# Jalebi_Bai0_1.net
KiCad netlist of a schematic drawn in EAGLE
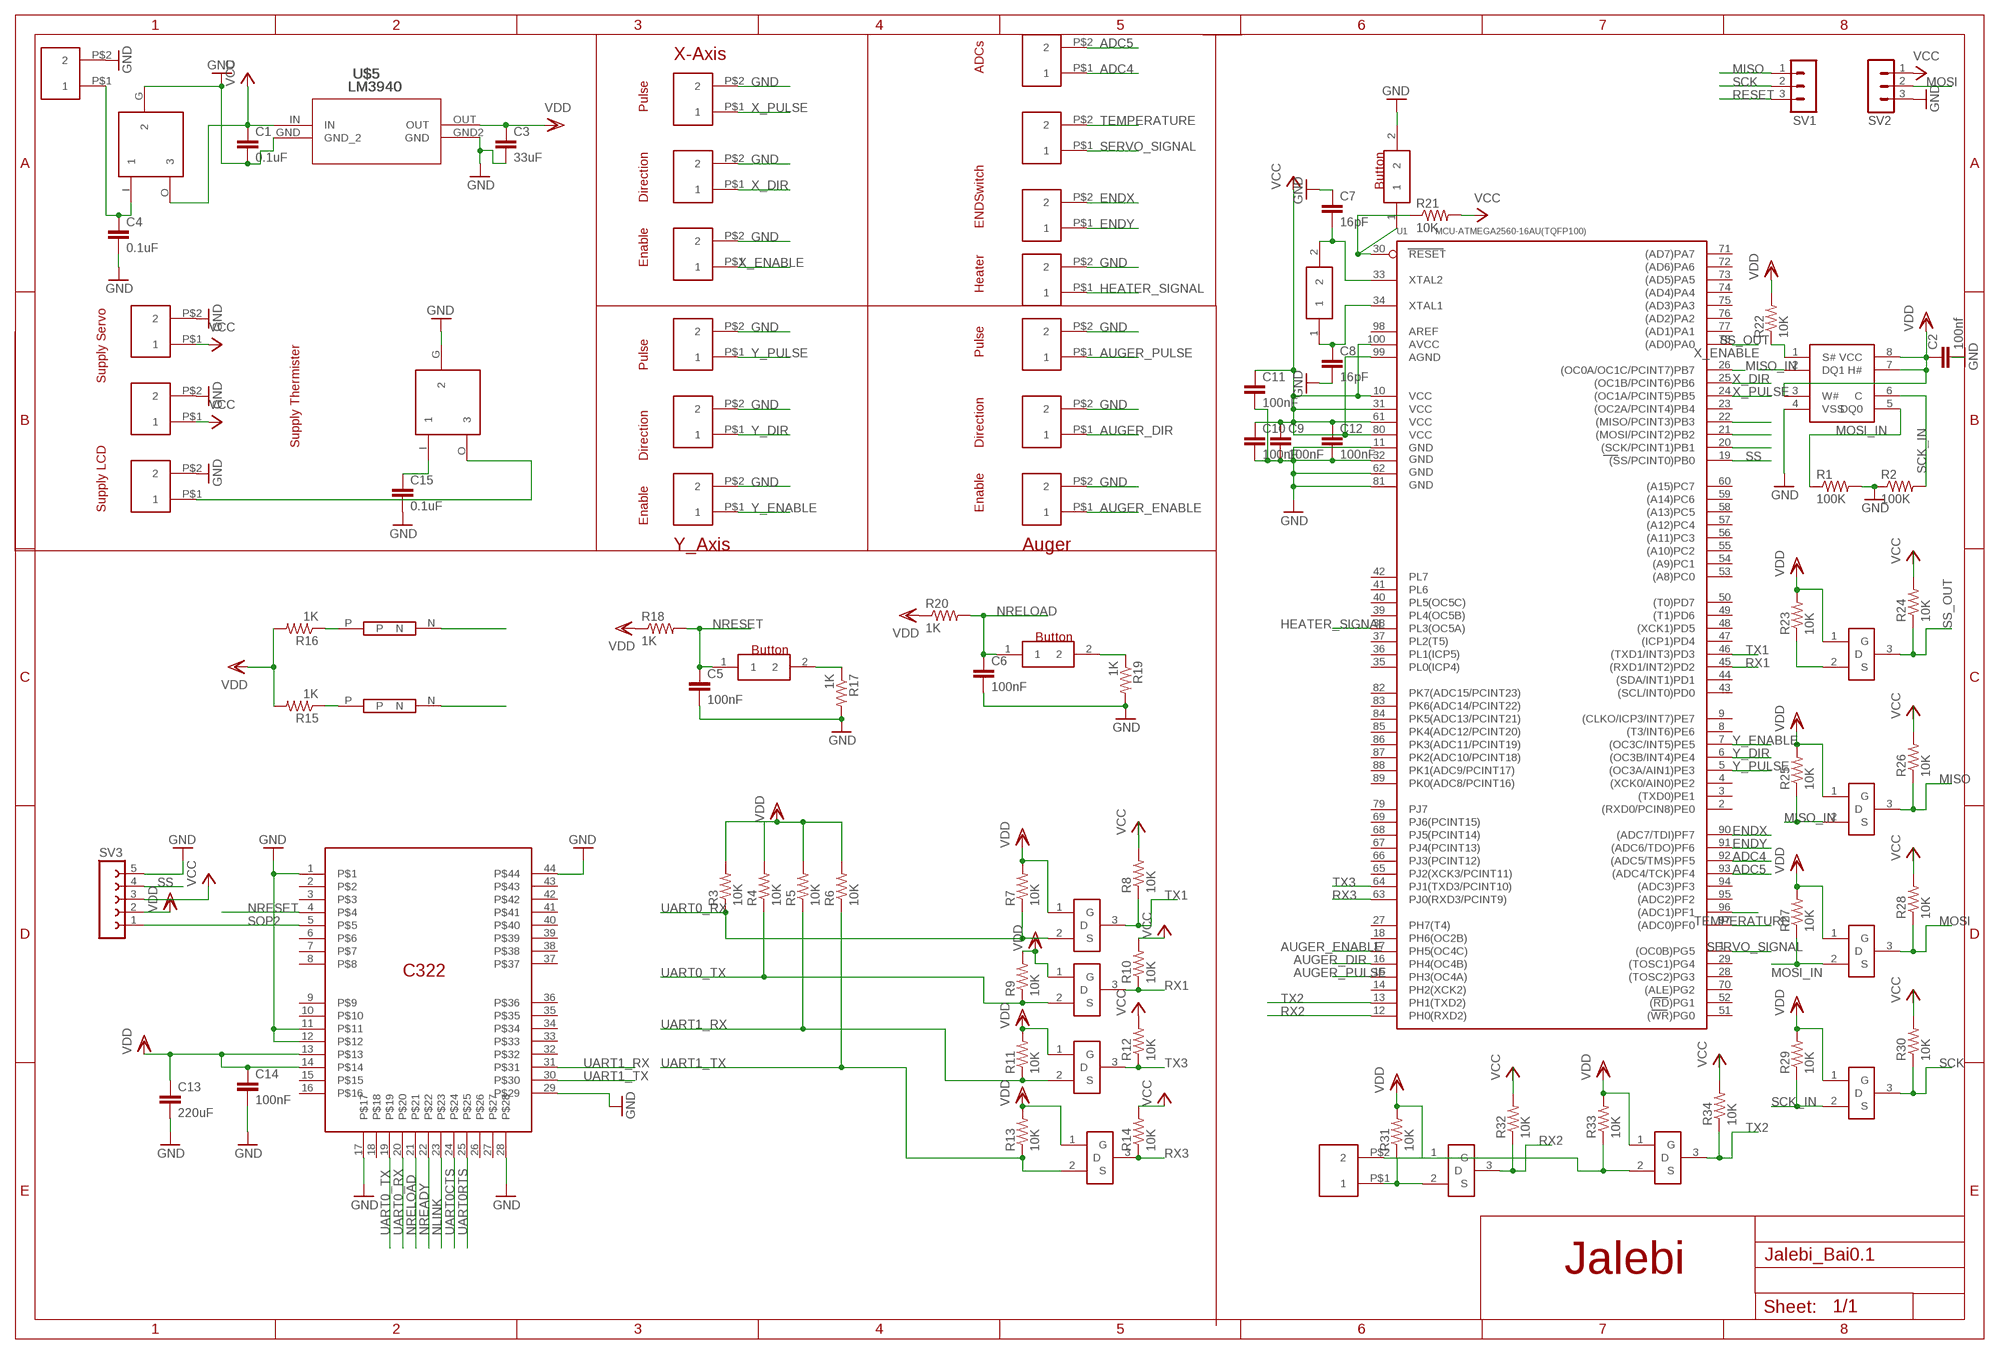
[diagram p0: schematic, sheet 1]

(export (version "E")
  (design (tool "Eeschema 10.0.6"))
  (components
    (comp (ref "C1")
      (value "0.1uF")
      (footprint "eagle-import:C0805")
      (libsource (lib "eagle-import") (part "C-EUC0805"))
    )
    (comp (ref "C2")
      (value "100nf")
      (footprint "eagle-import:C0805")
      (libsource (lib "eagle-import") (part "C-EUC0805"))
    )
    (comp (ref "C3")
      (value "33uF")
      (footprint "eagle-import:C0805")
      (libsource (lib "eagle-import") (part "C-EUC0805"))
    )
    (comp (ref "C4")
      (value "0.1uF")
      (footprint "eagle-import:C0805")
      (libsource (lib "eagle-import") (part "C-EUC0805"))
    )
    (comp (ref "C5")
      (value "100nF")
      (footprint "eagle-import:C0805")
      (libsource (lib "eagle-import") (part "C-EUC0805"))
    )
    (comp (ref "C6")
      (value "100nF")
      (footprint "eagle-import:C0805")
      (libsource (lib "eagle-import") (part "C-EUC0805"))
    )
    (comp (ref "C7")
      (value "16pF")
      (footprint "eagle-import:C0805")
      (libsource (lib "eagle-import") (part "C-EUC0805"))
    )
    (comp (ref "C8")
      (value "16pF")
      (footprint "eagle-import:C0805")
      (libsource (lib "eagle-import") (part "C-EUC0805"))
    )
    (comp (ref "C9")
      (value "100nF")
      (footprint "eagle-import:C0805")
      (libsource (lib "eagle-import") (part "C-EUC0805"))
    )
    (comp (ref "C10")
      (value "100nF")
      (footprint "eagle-import:C0805")
      (libsource (lib "eagle-import") (part "C-EUC0805"))
    )
    (comp (ref "C11")
      (value "100nF")
      (footprint "eagle-import:C0805")
      (libsource (lib "eagle-import") (part "C-EUC0805"))
    )
    (comp (ref "C12")
      (value "100nF")
      (footprint "eagle-import:C0805")
      (libsource (lib "eagle-import") (part "C-EUC0805"))
    )
    (comp (ref "C13")
      (value "220uF")
      (footprint "eagle-import:C0805")
      (libsource (lib "eagle-import") (part "C-EUC0805"))
    )
    (comp (ref "C14")
      (value "100nF")
      (footprint "eagle-import:C0805")
      (libsource (lib "eagle-import") (part "C-EUC0805"))
    )
    (comp (ref "C15")
      (value "0.1uF")
      (footprint "eagle-import:C0805")
      (libsource (lib "eagle-import") (part "C-EUC0805"))
    )
    (comp (ref "R1")
      (value "100K")
      (footprint "eagle-import:R0805")
      (libsource (lib "eagle-import") (part "R-US_R0805"))
    )
    (comp (ref "R2")
      (value "100K")
      (footprint "eagle-import:R0805")
      (libsource (lib "eagle-import") (part "R-US_R0805"))
    )
    (comp (ref "R3")
      (value "10K")
      (footprint "eagle-import:R0805")
      (libsource (lib "eagle-import") (part "R-US_R0805"))
    )
    (comp (ref "R4")
      (value "10K")
      (footprint "eagle-import:R0805")
      (libsource (lib "eagle-import") (part "R-US_R0805"))
    )
    (comp (ref "R5")
      (value "10K")
      (footprint "eagle-import:R0805")
      (libsource (lib "eagle-import") (part "R-US_R0805"))
    )
    (comp (ref "R6")
      (value "10K")
      (footprint "eagle-import:R0805")
      (libsource (lib "eagle-import") (part "R-US_R0805"))
    )
    (comp (ref "R7")
      (value "10K")
      (footprint "eagle-import:R0805")
      (libsource (lib "eagle-import") (part "R-US_R0805"))
    )
    (comp (ref "R8")
      (value "10K")
      (footprint "eagle-import:R0805")
      (libsource (lib "eagle-import") (part "R-US_R0805"))
    )
    (comp (ref "R9")
      (value "10K")
      (footprint "eagle-import:R0805")
      (libsource (lib "eagle-import") (part "R-US_R0805"))
    )
    (comp (ref "R10")
      (value "10K")
      (footprint "eagle-import:R0805")
      (libsource (lib "eagle-import") (part "R-US_R0805"))
    )
    (comp (ref "R11")
      (value "10K")
      (footprint "eagle-import:R0805")
      (libsource (lib "eagle-import") (part "R-US_R0805"))
    )
    (comp (ref "R12")
      (value "10K")
      (footprint "eagle-import:R0805")
      (libsource (lib "eagle-import") (part "R-US_R0805"))
    )
    (comp (ref "R13")
      (value "10K")
      (footprint "eagle-import:R0805")
      (libsource (lib "eagle-import") (part "R-US_R0805"))
    )
    (comp (ref "R14")
      (value "10K")
      (footprint "eagle-import:R0805")
      (libsource (lib "eagle-import") (part "R-US_R0805"))
    )
    (comp (ref "R15")
      (value "1K")
      (footprint "eagle-import:R0805")
      (libsource (lib "eagle-import") (part "R-US_R0805"))
    )
    (comp (ref "R16")
      (value "1K")
      (footprint "eagle-import:R0805")
      (libsource (lib "eagle-import") (part "R-US_R0805"))
    )
    (comp (ref "R17")
      (value "1K")
      (footprint "eagle-import:R0805")
      (libsource (lib "eagle-import") (part "R-US_R0805"))
    )
    (comp (ref "R18")
      (value "1K")
      (footprint "eagle-import:R0805")
      (libsource (lib "eagle-import") (part "R-US_R0805"))
    )
    (comp (ref "R19")
      (value "1K")
      (footprint "eagle-import:R0805")
      (libsource (lib "eagle-import") (part "R-US_R0805"))
    )
    (comp (ref "R20")
      (value "1K")
      (footprint "eagle-import:R0805")
      (libsource (lib "eagle-import") (part "R-US_R0805"))
    )
    (comp (ref "R21")
      (value "10K")
      (footprint "eagle-import:R0805")
      (libsource (lib "eagle-import") (part "R-US_R0805"))
    )
    (comp (ref "R22")
      (value "10K")
      (footprint "eagle-import:R0805")
      (libsource (lib "eagle-import") (part "R-US_R0805"))
    )
    (comp (ref "R23")
      (value "10K")
      (footprint "eagle-import:R0805")
      (libsource (lib "eagle-import") (part "R-US_R0805"))
    )
    (comp (ref "R24")
      (value "10K")
      (footprint "eagle-import:R0805")
      (libsource (lib "eagle-import") (part "R-US_R0805"))
    )
    (comp (ref "R25")
      (value "10K")
      (footprint "eagle-import:R0805")
      (libsource (lib "eagle-import") (part "R-US_R0805"))
    )
    (comp (ref "R26")
      (value "10K")
      (footprint "eagle-import:R0805")
      (libsource (lib "eagle-import") (part "R-US_R0805"))
    )
    (comp (ref "R27")
      (value "10K")
      (footprint "eagle-import:R0805")
      (libsource (lib "eagle-import") (part "R-US_R0805"))
    )
    (comp (ref "R28")
      (value "10K")
      (footprint "eagle-import:R0805")
      (libsource (lib "eagle-import") (part "R-US_R0805"))
    )
    (comp (ref "R29")
      (value "10K")
      (footprint "eagle-import:R0805")
      (libsource (lib "eagle-import") (part "R-US_R0805"))
    )
    (comp (ref "R30")
      (value "10K")
      (footprint "eagle-import:R0805")
      (libsource (lib "eagle-import") (part "R-US_R0805"))
    )
    (comp (ref "R31")
      (value "10K")
      (footprint "eagle-import:R0805")
      (libsource (lib "eagle-import") (part "R-US_R0805"))
    )
    (comp (ref "R32")
      (value "10K")
      (footprint "eagle-import:R0805")
      (libsource (lib "eagle-import") (part "R-US_R0805"))
    )
    (comp (ref "R33")
      (value "10K")
      (footprint "eagle-import:R0805")
      (libsource (lib "eagle-import") (part "R-US_R0805"))
    )
    (comp (ref "R34")
      (value "10K")
      (footprint "eagle-import:R0805")
      (libsource (lib "eagle-import") (part "R-US_R0805"))
    )
    (comp (ref "SUPPLY_LCD")
      (value "TERMINALBLOCK2PIN")
      (footprint "eagle-import:TERMINALBLOCK2")
      (libsource (lib "eagle-import") (part "TERMINALBLOCK2PIN"))
    )
    (comp (ref "SUPPLY_SERVO")
      (value "TERMINALBLOCK2PIN")
      (footprint "eagle-import:TERMINALBLOCK2")
      (libsource (lib "eagle-import") (part "TERMINALBLOCK2PIN"))
    )
    (comp (ref "SUPPLY_THERMISTER")
      (value "TERMINALBLOCK2PIN")
      (footprint "eagle-import:TERMINALBLOCK2")
      (libsource (lib "eagle-import") (part "TERMINALBLOCK2PIN"))
    )
    (comp (ref "SV1")
      (value "MA03-1")
      (footprint "eagle-import:MA03-1")
      (libsource (lib "eagle-import") (part "MA03-1"))
    )
    (comp (ref "SV2")
      (value "MA03-1")
      (footprint "eagle-import:MA03-1")
      (libsource (lib "eagle-import") (part "MA03-1"))
    )
    (comp (ref "SV3")
      (value "FE05-1")
      (footprint "eagle-import:FE05-1")
      (libsource (lib "eagle-import") (part "FE05-1"))
    )
    (comp (ref "U$1")
      (value "C322STD")
      (footprint "eagle-import:C322")
      (libsource (lib "eagle-import") (part "C322STD"))
    )
    (comp (ref "U$2")
      (value "7805")
      (footprint "eagle-import:7805")
      (libsource (lib "eagle-import") (part "7805"))
    )
    (comp (ref "U$3")
      (value "TERMINALBLOCK2PIN")
      (footprint "eagle-import:TERMINALBLOCK2")
      (libsource (lib "eagle-import") (part "TERMINALBLOCK2PIN"))
    )
    (comp (ref "U$4")
      (value "FLASHM25PX80")
      (footprint "eagle-import:SO08")
      (libsource (lib "eagle-import") (part "FLASHM25PX80"))
    )
    (comp (ref "U$5")
      (value "LM3940")
      (footprint "eagle-import:MP04A")
      (libsource (lib "eagle-import") (part "LM3940"))
    )
    (comp (ref "U$6")
      (value "BSS138")
      (footprint "eagle-import:SOT23")
      (libsource (lib "eagle-import") (part "BSS138"))
    )
    (comp (ref "U$7")
      (value "BSS138")
      (footprint "eagle-import:SOT23")
      (libsource (lib "eagle-import") (part "BSS138"))
    )
    (comp (ref "U$8")
      (value "BSS138")
      (footprint "eagle-import:SOT23")
      (libsource (lib "eagle-import") (part "BSS138"))
    )
    (comp (ref "U$9")
      (value "BSS138")
      (footprint "eagle-import:SOT23")
      (libsource (lib "eagle-import") (part "BSS138"))
    )
    (comp (ref "U$10")
      (value "LED(805)")
      (footprint "eagle-import:LED(805)")
      (libsource (lib "eagle-import") (part "LED(805)"))
    )
    (comp (ref "U$11")
      (value "LED(805)")
      (footprint "eagle-import:LED(805)")
      (libsource (lib "eagle-import") (part "LED(805)"))
    )
    (comp (ref "U$12")
      (value "BUTTON")
      (footprint "eagle-import:BUTTON")
      (libsource (lib "eagle-import") (part "BUTTON"))
    )
    (comp (ref "U$13")
      (value "BUTTON")
      (footprint "eagle-import:BUTTON")
      (libsource (lib "eagle-import") (part "BUTTON"))
    )
    (comp (ref "U$14")
      (value "TERMINALBLOCK2PIN")
      (footprint "eagle-import:TERMINALBLOCK2")
      (libsource (lib "eagle-import") (part "TERMINALBLOCK2PIN"))
    )
    (comp (ref "U$15")
      (value "CRYSTAL")
      (footprint "eagle-import:CRYSTAL")
      (libsource (lib "eagle-import") (part "CRYSTAL"))
    )
    (comp (ref "U$16")
      (value "BUTTON")
      (footprint "eagle-import:BUTTON")
      (libsource (lib "eagle-import") (part "BUTTON"))
    )
    (comp (ref "U$17")
      (value "BSS138")
      (footprint "eagle-import:SOT23")
      (libsource (lib "eagle-import") (part "BSS138"))
    )
    (comp (ref "U$18")
      (value "BSS138")
      (footprint "eagle-import:SOT23")
      (libsource (lib "eagle-import") (part "BSS138"))
    )
    (comp (ref "U$19")
      (value "BSS138")
      (footprint "eagle-import:SOT23")
      (libsource (lib "eagle-import") (part "BSS138"))
    )
    (comp (ref "U$20")
      (value "BSS138")
      (footprint "eagle-import:SOT23")
      (libsource (lib "eagle-import") (part "BSS138"))
    )
    (comp (ref "U$21")
      (value "BSS138")
      (footprint "eagle-import:SOT23")
      (libsource (lib "eagle-import") (part "BSS138"))
    )
    (comp (ref "U$22")
      (value "BSS138")
      (footprint "eagle-import:SOT23")
      (libsource (lib "eagle-import") (part "BSS138"))
    )
    (comp (ref "U$23")
      (value "TERMINALBLOCK2PIN")
      (footprint "eagle-import:TERMINALBLOCK2")
      (libsource (lib "eagle-import") (part "TERMINALBLOCK2PIN"))
    )
    (comp (ref "U$24")
      (value "TERMINALBLOCK2PIN")
      (footprint "eagle-import:TERMINALBLOCK2")
      (libsource (lib "eagle-import") (part "TERMINALBLOCK2PIN"))
    )
    (comp (ref "U$25")
      (value "7805")
      (footprint "eagle-import:7805")
      (libsource (lib "eagle-import") (part "7805"))
    )
    (comp (ref "U$26")
      (value "TERMINALBLOCK2PIN")
      (footprint "eagle-import:TERMINALBLOCK2")
      (libsource (lib "eagle-import") (part "TERMINALBLOCK2PIN"))
    )
    (comp (ref "U$27")
      (value "TERMINALBLOCK2PIN")
      (footprint "eagle-import:TERMINALBLOCK2")
      (libsource (lib "eagle-import") (part "TERMINALBLOCK2PIN"))
    )
    (comp (ref "U$28")
      (value "TERMINALBLOCK2PIN")
      (footprint "eagle-import:TERMINALBLOCK2")
      (libsource (lib "eagle-import") (part "TERMINALBLOCK2PIN"))
    )
    (comp (ref "U$29")
      (value "TERMINALBLOCK2PIN")
      (footprint "eagle-import:TERMINALBLOCK2")
      (libsource (lib "eagle-import") (part "TERMINALBLOCK2PIN"))
    )
    (comp (ref "U$30")
      (value "TERMINALBLOCK2PIN")
      (footprint "eagle-import:TERMINALBLOCK2")
      (libsource (lib "eagle-import") (part "TERMINALBLOCK2PIN"))
    )
    (comp (ref "U$31")
      (value "TERMINALBLOCK2PIN")
      (footprint "eagle-import:TERMINALBLOCK2")
      (libsource (lib "eagle-import") (part "TERMINALBLOCK2PIN"))
    )
    (comp (ref "U$32")
      (value "TERMINALBLOCK2PIN")
      (footprint "eagle-import:TERMINALBLOCK2")
      (libsource (lib "eagle-import") (part "TERMINALBLOCK2PIN"))
    )
    (comp (ref "U$34")
      (value "TERMINALBLOCK2PIN")
      (footprint "eagle-import:TERMINALBLOCK2")
      (libsource (lib "eagle-import") (part "TERMINALBLOCK2PIN"))
    )
    (comp (ref "U$35")
      (value "TERMINALBLOCK2PIN")
      (footprint "eagle-import:TERMINALBLOCK2")
      (libsource (lib "eagle-import") (part "TERMINALBLOCK2PIN"))
    )
    (comp (ref "U$36")
      (value "TERMINALBLOCK2PIN")
      (footprint "eagle-import:TERMINALBLOCK2")
      (libsource (lib "eagle-import") (part "TERMINALBLOCK2PIN"))
    )
    (comp (ref "U$37")
      (value "TERMINALBLOCK2PIN")
      (footprint "eagle-import:TERMINALBLOCK2")
      (libsource (lib "eagle-import") (part "TERMINALBLOCK2PIN"))
    )
    (comp (ref "U1")
      (value "MCU-ATMEGA2560-16AU(TQFP100)")
      (footprint "eagle-import:TQFP100-0.5-14X14MM")
      (fields (field (name "MF") "Atmel") (field (name "MP") "ATMEGA2560-16AU"))
      (libsource (lib "eagle-import") (part "MCU-ATMEGA2560-16AU(TQFP100)"))
    )
  )
  (nets
    (net (code "1") (name "/ADC4") (class "Default")
      (node (ref "U$24") (pin "P$1") (pinfunction "1_P$1") (pintype "bidirectional"))
      (node (ref "U1") (pin "92") (pinfunction "(ADC5/TMS)PF5_92") (pintype "bidirectional"))
    )
    (net (code "2") (name "/ADC5") (class "Default")
      (node (ref "U$24") (pin "P$2") (pinfunction "2_P$2") (pintype "bidirectional"))
      (node (ref "U1") (pin "93") (pinfunction "(ADC4/TCK)PF4_93") (pintype "bidirectional"))
    )
    (net (code "3") (name "/AUGER_DIR") (class "Default")
      (node (ref "U$36") (pin "P$1") (pinfunction "1_P$1") (pintype "bidirectional"))
      (node (ref "U1") (pin "16") (pinfunction "PH4(OC4B)_16") (pintype "bidirectional"))
    )
    (net (code "4") (name "/AUGER_ENABLE") (class "Default")
      (node (ref "U$37") (pin "P$1") (pinfunction "1_P$1") (pintype "bidirectional"))
      (node (ref "U1") (pin "17") (pinfunction "PH5(OC4C)_17") (pintype "bidirectional"))
    )
    (net (code "5") (name "/AUGER_PULSE") (class "Default")
      (node (ref "U$35") (pin "P$1") (pinfunction "1_P$1") (pintype "bidirectional"))
      (node (ref "U1") (pin "15") (pinfunction "PH3(OC4A)_15") (pintype "bidirectional"))
    )
    (net (code "6") (name "/ENDX") (class "Default")
      (node (ref "U$23") (pin "P$2") (pinfunction "2_P$2") (pintype "bidirectional"))
      (node (ref "U1") (pin "90") (pinfunction "(ADC7/TDI)PF7_90") (pintype "bidirectional"))
    )
    (net (code "7") (name "/ENDY") (class "Default")
      (node (ref "U$23") (pin "P$1") (pinfunction "1_P$1") (pintype "bidirectional"))
      (node (ref "U1") (pin "91") (pinfunction "(ADC6/TDO)PF6_91") (pintype "bidirectional"))
    )
    (net (code "8") (name "/HEATER_SIGNAL") (class "Default")
      (node (ref "U$34") (pin "P$1") (pinfunction "1_P$1") (pintype "bidirectional"))
      (node (ref "U1") (pin "38") (pinfunction "PL3(OC5A)_38") (pintype "bidirectional"))
    )
    (net (code "9") (name "/MISO") (class "Default")
      (node (ref "R26") (pin "1") (pinfunction "1_1") (pintype "passive"))
      (node (ref "SV1") (pin "1") (pinfunction "1_1") (pintype "passive"))
      (node (ref "U$18") (pin "3") (pinfunction "D_3") (pintype "bidirectional"))
      (node (ref "U1") (pin "22") (pinfunction "(MISO/PCINT3)PB3_22") (pintype "bidirectional"))
    )
    (net (code "10") (name "/MISO_IN") (class "Default")
      (node (ref "R25") (pin "1") (pinfunction "1_1") (pintype "passive"))
      (node (ref "U$18") (pin "2") (pinfunction "S_2") (pintype "bidirectional"))
      (node (ref "U$4") (pin "2") (pinfunction "DQ1_2") (pintype "bidirectional"))
    )
    (net (code "11") (name "/MOSI") (class "Default")
      (node (ref "R28") (pin "1") (pinfunction "1_1") (pintype "passive"))
      (node (ref "SV2") (pin "2") (pinfunction "2_2") (pintype "passive"))
      (node (ref "U$19") (pin "3") (pinfunction "D_3") (pintype "bidirectional"))
      (node (ref "U1") (pin "21") (pinfunction "(MOSI/PCINT2)PB2_21") (pintype "bidirectional"))
    )
    (net (code "12") (name "/MOSI_IN") (class "Default")
      (node (ref "R1") (pin "1") (pinfunction "1_1") (pintype "passive"))
      (node (ref "R27") (pin "1") (pinfunction "1_1") (pintype "passive"))
      (node (ref "U$19") (pin "2") (pinfunction "S_2") (pintype "bidirectional"))
      (node (ref "U$4") (pin "5") (pinfunction "DQ0_5") (pintype "bidirectional"))
    )
    (net (code "13") (name "/N$5") (class "Default")
      (node (ref "C15") (pin "1") (pinfunction "1_1") (pintype "passive"))
      (node (ref "C4") (pin "1") (pinfunction "1_1") (pintype "passive"))
      (node (ref "U$2") (pin "I") (pinfunction "1_I") (pintype "bidirectional"))
      (node (ref "U$25") (pin "I") (pinfunction "1_I") (pintype "bidirectional"))
      (node (ref "U$3") (pin "P$1") (pinfunction "1_P$1") (pintype "bidirectional"))
    )
    (net (code "14") (name "/NLINK") (class "Default")
      (node (ref "U$1") (pin "23") (pinfunction "P$23_23") (pintype "bidirectional"))
      (node (ref "U$10") (pin "N") (pinfunction "N_N") (pintype "bidirectional"))
    )
    (net (code "15") (name "/NREADY") (class "Default")
      (node (ref "U$1") (pin "22") (pinfunction "P$22_22") (pintype "bidirectional"))
      (node (ref "U$11") (pin "N") (pinfunction "N_N") (pintype "bidirectional"))
    )
    (net (code "16") (name "/NRELOAD") (class "Default")
      (node (ref "C6") (pin "1") (pinfunction "1_1") (pintype "passive"))
      (node (ref "R20") (pin "2") (pinfunction "2_2") (pintype "passive"))
      (node (ref "U$1") (pin "21") (pinfunction "P$21_21") (pintype "bidirectional"))
      (node (ref "U$13") (pin "1") (pinfunction "1_1") (pintype "bidirectional"))
    )
    (net (code "17") (name "/NRESET") (class "Default")
      (node (ref "C5") (pin "1") (pinfunction "1_1") (pintype "passive"))
      (node (ref "R18") (pin "2") (pinfunction "2_2") (pintype "passive"))
      (node (ref "U$1") (pin "4") (pinfunction "P$4_4") (pintype "bidirectional"))
      (node (ref "U$12") (pin "1") (pinfunction "1_1") (pintype "bidirectional"))
    )
    (net (code "18") (name "/RESET") (class "Default")
      (node (ref "R21") (pin "1") (pinfunction "1_1") (pintype "passive"))
      (node (ref "SV1") (pin "3") (pinfunction "3_3") (pintype "passive"))
      (node (ref "U$16") (pin "1") (pinfunction "1_1") (pintype "bidirectional"))
      (node (ref "U1") (pin "30") (pinfunction "RESET_30") (pintype "input"))
    )
    (net (code "19") (name "/RX1") (class "Default")
      (node (ref "R10") (pin "1") (pinfunction "1_1") (pintype "passive"))
      (node (ref "U$7") (pin "3") (pinfunction "D_3") (pintype "bidirectional"))
      (node (ref "U1") (pin "45") (pinfunction "(RXD1/INT2)PD2_45") (pintype "bidirectional"))
    )
    (net (code "20") (name "/RX2") (class "Default")
      (node (ref "R32") (pin "1") (pinfunction "1_1") (pintype "passive"))
      (node (ref "U$21") (pin "3") (pinfunction "D_3") (pintype "bidirectional"))
      (node (ref "U1") (pin "12") (pinfunction "PH0(RXD2)_12") (pintype "bidirectional"))
    )
    (net (code "21") (name "/RX3") (class "Default")
      (node (ref "R14") (pin "1") (pinfunction "1_1") (pintype "passive"))
      (node (ref "U$9") (pin "3") (pinfunction "D_3") (pintype "bidirectional"))
      (node (ref "U1") (pin "63") (pinfunction "PJ0(RXD3/PCINT9)_63") (pintype "bidirectional"))
    )
    (net (code "22") (name "/SCK") (class "Default")
      (node (ref "R30") (pin "1") (pinfunction "1_1") (pintype "passive"))
      (node (ref "SV1") (pin "2") (pinfunction "2_2") (pintype "passive"))
      (node (ref "U$20") (pin "3") (pinfunction "D_3") (pintype "bidirectional"))
      (node (ref "U1") (pin "20") (pinfunction "(SCK/PCINT1)PB1_20") (pintype "bidirectional"))
    )
    (net (code "23") (name "/SCK_IN") (class "Default")
      (node (ref "R2") (pin "2") (pinfunction "2_2") (pintype "passive"))
      (node (ref "R29") (pin "1") (pinfunction "1_1") (pintype "passive"))
      (node (ref "U$20") (pin "2") (pinfunction "S_2") (pintype "bidirectional"))
      (node (ref "U$4") (pin "6") (pinfunction "C_6") (pintype "bidirectional"))
    )
    (net (code "24") (name "/SERVO_SIGNAL") (class "Default")
      (node (ref "U$32") (pin "P$1") (pinfunction "1_P$1") (pintype "bidirectional"))
      (node (ref "U1") (pin "1") (pinfunction "(OC0B)PG5_1") (pintype "bidirectional"))
    )
    (net (code "25") (name "/SOP2") (class "Default")
      (node (ref "SV3") (pin "1") (pinfunction "1_1") (pintype "passive"))
      (node (ref "U$1") (pin "5") (pinfunction "P$5_5") (pintype "bidirectional"))
    )
    (net (code "26") (name "/SS") (class "Default")
      (node (ref "SV3") (pin "4") (pinfunction "4_4") (pintype "passive"))
      (node (ref "U1") (pin "19") (pinfunction "(SS/PCINT0)PB0_19") (pintype "bidirectional"))
    )
    (net (code "27") (name "/SS_IN") (class "Default")
      (node (ref "R22") (pin "1") (pinfunction "1_1") (pintype "passive"))
      (node (ref "R23") (pin "1") (pinfunction "1_1") (pintype "passive"))
      (node (ref "U$17") (pin "2") (pinfunction "S_2") (pintype "bidirectional"))
      (node (ref "U$4") (pin "1") (pinfunction "S#_1") (pintype "bidirectional"))
    )
    (net (code "28") (name "/SS_OUT") (class "Default")
      (node (ref "R24") (pin "1") (pinfunction "1_1") (pintype "passive"))
      (node (ref "U$17") (pin "3") (pinfunction "D_3") (pintype "bidirectional"))
      (node (ref "U1") (pin "78") (pinfunction "(AD0)PA0_78") (pintype "bidirectional"))
    )
    (net (code "29") (name "/TEMPERATURE") (class "Default")
      (node (ref "U$32") (pin "P$2") (pinfunction "2_P$2") (pintype "bidirectional"))
      (node (ref "U1") (pin "97") (pinfunction "(ADC0)PF0_97") (pintype "bidirectional"))
    )
    (net (code "30") (name "/TX1") (class "Default")
      (node (ref "R8") (pin "1") (pinfunction "1_1") (pintype "passive"))
      (node (ref "U$6") (pin "3") (pinfunction "D_3") (pintype "bidirectional"))
      (node (ref "U1") (pin "46") (pinfunction "(TXD1/INT3)PD3_46") (pintype "bidirectional"))
    )
    (net (code "31") (name "/TX2") (class "Default")
      (node (ref "R34") (pin "1") (pinfunction "1_1") (pintype "passive"))
      (node (ref "U$22") (pin "3") (pinfunction "D_3") (pintype "bidirectional"))
      (node (ref "U1") (pin "13") (pinfunction "PH1(TXD2)_13") (pintype "bidirectional"))
    )
    (net (code "32") (name "/TX3") (class "Default")
      (node (ref "R12") (pin "1") (pinfunction "1_1") (pintype "passive"))
      (node (ref "U$8") (pin "3") (pinfunction "D_3") (pintype "bidirectional"))
      (node (ref "U1") (pin "64") (pinfunction "PJ1(TXD3/PCINT10)_64") (pintype "bidirectional"))
    )
    (net (code "33") (name "/UART0CTS") (class "Default")
      (node (ref "U$1") (pin "24") (pinfunction "P$24_24") (pintype "bidirectional"))
    )
    (net (code "34") (name "/UART0RTS") (class "Default")
      (node (ref "U$1") (pin "25") (pinfunction "P$25_25") (pintype "bidirectional"))
    )
    (net (code "35") (name "/UART0_RX") (class "Default")
      (node (ref "R3") (pin "1") (pinfunction "1_1") (pintype "passive"))
      (node (ref "R7") (pin "1") (pinfunction "1_1") (pintype "passive"))
      (node (ref "U$1") (pin "20") (pinfunction "P$20_20") (pintype "bidirectional"))
      (node (ref "U$6") (pin "2") (pinfunction "S_2") (pintype "bidirectional"))
    )
    (net (code "36") (name "/UART0_TX") (class "Default")
      (node (ref "R4") (pin "1") (pinfunction "1_1") (pintype "passive"))
      (node (ref "R9") (pin "1") (pinfunction "1_1") (pintype "passive"))
      (node (ref "U$1") (pin "19") (pinfunction "P$19_19") (pintype "bidirectional"))
      (node (ref "U$7") (pin "2") (pinfunction "S_2") (pintype "bidirectional"))
    )
    (net (code "37") (name "/UART1_RX") (class "Default")
      (node (ref "R11") (pin "1") (pinfunction "1_1") (pintype "passive"))
      (node (ref "R5") (pin "1") (pinfunction "1_1") (pintype "passive"))
      (node (ref "U$1") (pin "31") (pinfunction "P$31_31") (pintype "bidirectional"))
      (node (ref "U$8") (pin "2") (pinfunction "S_2") (pintype "bidirectional"))
    )
    (net (code "38") (name "/UART1_TX") (class "Default")
      (node (ref "R13") (pin "1") (pinfunction "1_1") (pintype "passive"))
      (node (ref "R6") (pin "1") (pinfunction "1_1") (pintype "passive"))
      (node (ref "U$1") (pin "30") (pinfunction "P$30_30") (pintype "bidirectional"))
      (node (ref "U$9") (pin "2") (pinfunction "S_2") (pintype "bidirectional"))
    )
    (net (code "39") (name "/X_DIR") (class "Default")
      (node (ref "U$27") (pin "P$1") (pinfunction "1_P$1") (pintype "bidirectional"))
      (node (ref "U1") (pin "25") (pinfunction "(OC1B/PCINT6)PB6_25") (pintype "bidirectional"))
    )
    (net (code "40") (name "/X_ENABLE") (class "Default")
      (node (ref "U$28") (pin "P$1") (pinfunction "1_P$1") (pintype "bidirectional"))
      (node (ref "U1") (pin "26") (pinfunction "(OC0A/OC1C/PCINT7)PB7_26") (pintype "bidirectional"))
    )
    (net (code "41") (name "/X_PULSE") (class "Default")
      (node (ref "U$26") (pin "P$1") (pinfunction "1_P$1") (pintype "bidirectional"))
      (node (ref "U1") (pin "24") (pinfunction "(OC1A/PCINT5)PB5_24") (pintype "bidirectional"))
    )
    (net (code "42") (name "/Y_DIR") (class "Default")
      (node (ref "U$30") (pin "P$1") (pinfunction "1_P$1") (pintype "bidirectional"))
      (node (ref "U1") (pin "6") (pinfunction "(OC3B/INT4)PE4_6") (pintype "bidirectional"))
    )
    (net (code "43") (name "/Y_ENABLE") (class "Default")
      (node (ref "U$31") (pin "P$1") (pinfunction "1_P$1") (pintype "bidirectional"))
      (node (ref "U1") (pin "7") (pinfunction "(OC3C/INT5)PE5_7") (pintype "bidirectional"))
    )
    (net (code "44") (name "/Y_PULSE") (class "Default")
      (node (ref "U$29") (pin "P$1") (pinfunction "1_P$1") (pintype "bidirectional"))
      (node (ref "U1") (pin "5") (pinfunction "(OC3A/AIN1)PE3_5") (pintype "bidirectional"))
    )
    (net (code "45") (name "GND") (class "Default")
      (node (ref "C1") (pin "2") (pinfunction "2_2") (pintype "passive"))
      (node (ref "C10") (pin "2") (pinfunction "2_2") (pintype "passive"))
      (node (ref "C11") (pin "2") (pinfunction "2_2") (pintype "passive"))
      (node (ref "C12") (pin "2") (pinfunction "2_2") (pintype "passive"))
      (node (ref "C13") (pin "2") (pinfunction "2_2") (pintype "passive"))
      (node (ref "C14") (pin "2") (pinfunction "2_2") (pintype "passive"))
      (node (ref "C15") (pin "2") (pinfunction "2_2") (pintype "passive"))
      (node (ref "C2") (pin "2") (pinfunction "2_2") (pintype "passive"))
      (node (ref "C3") (pin "2") (pinfunction "2_2") (pintype "passive"))
      (node (ref "C4") (pin "2") (pinfunction "2_2") (pintype "passive"))
      (node (ref "C5") (pin "2") (pinfunction "2_2") (pintype "passive"))
      (node (ref "C6") (pin "2") (pinfunction "2_2") (pintype "passive"))
      (node (ref "C7") (pin "1") (pinfunction "1_1") (pintype "passive"))
      (node (ref "C8") (pin "2") (pinfunction "2_2") (pintype "passive"))
      (node (ref "C9") (pin "2") (pinfunction "2_2") (pintype "passive"))
      (node (ref "R1") (pin "2") (pinfunction "2_2") (pintype "passive"))
      (node (ref "R17") (pin "2") (pinfunction "2_2") (pintype "passive"))
      (node (ref "R19") (pin "2") (pinfunction "2_2") (pintype "passive"))
      (node (ref "R2") (pin "1") (pinfunction "1_1") (pintype "passive"))
      (node (ref "SUPPLY_LCD") (pin "P$2") (pinfunction "2_P$2") (pintype "bidirectional"))
      (node (ref "SUPPLY_SERVO") (pin "P$2") (pinfunction "2_P$2") (pintype "bidirectional"))
      (node (ref "SUPPLY_THERMISTER") (pin "P$2") (pinfunction "2_P$2") (pintype "bidirectional"))
      (node (ref "SV2") (pin "3") (pinfunction "3_3") (pintype "passive"))
      (node (ref "SV3") (pin "5") (pinfunction "5_5") (pintype "passive"))
      (node (ref "U$1") (pin "1") (pinfunction "P$1_1") (pintype "bidirectional"))
      (node (ref "U$1") (pin "11") (pinfunction "P$11_11") (pintype "bidirectional"))
      (node (ref "U$1") (pin "12") (pinfunction "P$12_12") (pintype "bidirectional"))
      (node (ref "U$1") (pin "17") (pinfunction "P$17_17") (pintype "bidirectional"))
      (node (ref "U$1") (pin "28") (pinfunction "P$28_28") (pintype "bidirectional"))
      (node (ref "U$1") (pin "29") (pinfunction "P$29_29") (pintype "bidirectional"))
      (node (ref "U$1") (pin "44") (pinfunction "P$44_44") (pintype "bidirectional"))
      (node (ref "U$16") (pin "2") (pinfunction "2_2") (pintype "bidirectional"))
      (node (ref "U$2") (pin "G") (pinfunction "2_G") (pintype "bidirectional"))
      (node (ref "U$25") (pin "G") (pinfunction "2_G") (pintype "bidirectional"))
      (node (ref "U$26") (pin "P$2") (pinfunction "2_P$2") (pintype "bidirectional"))
      (node (ref "U$27") (pin "P$2") (pinfunction "2_P$2") (pintype "bidirectional"))
      (node (ref "U$28") (pin "P$2") (pinfunction "2_P$2") (pintype "bidirectional"))
      (node (ref "U$29") (pin "P$2") (pinfunction "2_P$2") (pintype "bidirectional"))
      (node (ref "U$3") (pin "P$2") (pinfunction "2_P$2") (pintype "bidirectional"))
      (node (ref "U$30") (pin "P$2") (pinfunction "2_P$2") (pintype "bidirectional"))
      (node (ref "U$31") (pin "P$2") (pinfunction "2_P$2") (pintype "bidirectional"))
      (node (ref "U$34") (pin "P$2") (pinfunction "2_P$2") (pintype "bidirectional"))
      (node (ref "U$35") (pin "P$2") (pinfunction "2_P$2") (pintype "bidirectional"))
      (node (ref "U$36") (pin "P$2") (pinfunction "2_P$2") (pintype "bidirectional"))
      (node (ref "U$37") (pin "P$2") (pinfunction "2_P$2") (pintype "bidirectional"))
      (node (ref "U$4") (pin "4") (pinfunction "VSS_4") (pintype "bidirectional"))
      (node (ref "U$5") (pin "GND") (pinfunction "GND_2_GND") (pintype "passive"))
      (node (ref "U$5") (pin "GND2") (pinfunction "GND_GND2") (pintype "passive"))
      (node (ref "U1") (pin "11") (pinfunction "GND_11") (pintype "power_in"))
      (node (ref "U1") (pin "32") (pinfunction "GND1_32") (pintype "power_in"))
      (node (ref "U1") (pin "62") (pinfunction "GND2_62") (pintype "power_in"))
      (node (ref "U1") (pin "81") (pinfunction "GND3_81") (pintype "power_in"))
    )
    (net (code "46") (name "Net-(R15-Pad1)") (class "Default")
      (node (ref "R15") (pin "1") (pinfunction "1_1") (pintype "passive"))
      (node (ref "U$11") (pin "P") (pinfunction "P_P") (pintype "bidirectional"))
    )
    (net (code "47") (name "Net-(R16-Pad1)") (class "Default")
      (node (ref "R16") (pin "1") (pinfunction "1_1") (pintype "passive"))
      (node (ref "U$10") (pin "P") (pinfunction "P_P") (pintype "bidirectional"))
    )
    (net (code "48") (name "Net-(R17-Pad1)") (class "Default")
      (node (ref "R17") (pin "1") (pinfunction "1_1") (pintype "passive"))
      (node (ref "U$12") (pin "2") (pinfunction "2_2") (pintype "bidirectional"))
    )
    (net (code "49") (name "Net-(R19-Pad1)") (class "Default")
      (node (ref "R19") (pin "1") (pinfunction "1_1") (pintype "passive"))
      (node (ref "U$13") (pin "2") (pinfunction "2_2") (pintype "bidirectional"))
    )
    (net (code "50") (name "Net-(SUPPLY_LCD-1)") (class "Default")
      (node (ref "SUPPLY_LCD") (pin "P$1") (pinfunction "1_P$1") (pintype "bidirectional"))
      (node (ref "U$25") (pin "O") (pinfunction "3_O") (pintype "bidirectional"))
    )
    (net (code "51") (name "Net-(U$14-1)") (class "Default")
      (node (ref "R31") (pin "1") (pinfunction "1_1") (pintype "passive"))
      (node (ref "U$14") (pin "P$1") (pinfunction "1_P$1") (pintype "bidirectional"))
      (node (ref "U$21") (pin "2") (pinfunction "S_2") (pintype "bidirectional"))
    )
    (net (code "52") (name "Net-(U$14-2)") (class "Default")
      (node (ref "R33") (pin "1") (pinfunction "1_1") (pintype "passive"))
      (node (ref "U$14") (pin "P$2") (pinfunction "2_P$2") (pintype "bidirectional"))
      (node (ref "U$22") (pin "2") (pinfunction "S_2") (pintype "bidirectional"))
    )
    (net (code "53") (name "Net-(U1-XTAL1)") (class "Default")
      (node (ref "C8") (pin "1") (pinfunction "1_1") (pintype "passive"))
      (node (ref "U$15") (pin "1") (pinfunction "1_1") (pintype "bidirectional"))
      (node (ref "U1") (pin "34") (pinfunction "XTAL1_34") (pintype "input"))
    )
    (net (code "54") (name "Net-(U1-XTAL2)") (class "Default")
      (node (ref "C7") (pin "2") (pinfunction "2_2") (pintype "passive"))
      (node (ref "U$15") (pin "2") (pinfunction "2_2") (pintype "bidirectional"))
      (node (ref "U1") (pin "33") (pinfunction "XTAL2_33") (pintype "output"))
    )
    (net (code "55") (name "VCC") (class "Default")
      (node (ref "C1") (pin "1") (pinfunction "1_1") (pintype "passive"))
      (node (ref "C10") (pin "1") (pinfunction "1_1") (pintype "passive"))
      (node (ref "C11") (pin "1") (pinfunction "1_1") (pintype "passive"))
      (node (ref "C12") (pin "1") (pinfunction "1_1") (pintype "passive"))
      (node (ref "C9") (pin "1") (pinfunction "1_1") (pintype "passive"))
      (node (ref "R10") (pin "2") (pinfunction "2_2") (pintype "passive"))
      (node (ref "R12") (pin "2") (pinfunction "2_2") (pintype "passive"))
      (node (ref "R14") (pin "2") (pinfunction "2_2") (pintype "passive"))
      (node (ref "R21") (pin "2") (pinfunction "2_2") (pintype "passive"))
      (node (ref "R24") (pin "2") (pinfunction "2_2") (pintype "passive"))
      (node (ref "R26") (pin "2") (pinfunction "2_2") (pintype "passive"))
      (node (ref "R28") (pin "2") (pinfunction "2_2") (pintype "passive"))
      (node (ref "R30") (pin "2") (pinfunction "2_2") (pintype "passive"))
      (node (ref "R32") (pin "2") (pinfunction "2_2") (pintype "passive"))
      (node (ref "R34") (pin "2") (pinfunction "2_2") (pintype "passive"))
      (node (ref "R8") (pin "2") (pinfunction "2_2") (pintype "passive"))
      (node (ref "SUPPLY_SERVO") (pin "P$1") (pinfunction "1_P$1") (pintype "bidirectional"))
      (node (ref "SUPPLY_THERMISTER") (pin "P$1") (pinfunction "1_P$1") (pintype "bidirectional"))
      (node (ref "SV2") (pin "1") (pinfunction "1_1") (pintype "passive"))
      (node (ref "SV3") (pin "3") (pinfunction "3_3") (pintype "passive"))
      (node (ref "U$2") (pin "O") (pinfunction "3_O") (pintype "bidirectional"))
      (node (ref "U$5") (pin "IN") (pinfunction "IN_IN") (pintype "input"))
      (node (ref "U1") (pin "10") (pinfunction "VCC_10") (pintype "power_in"))
      (node (ref "U1") (pin "100") (pinfunction "AVCC_100") (pintype "power_in"))
      (node (ref "U1") (pin "31") (pinfunction "VCC1_31") (pintype "power_in"))
      (node (ref "U1") (pin "61") (pinfunction "VCC2_61") (pintype "power_in"))
      (node (ref "U1") (pin "80") (pinfunction "VCC3_80") (pintype "power_in"))
      (node (ref "U1") (pin "99") (pinfunction "AGND_99") (pintype "power_in"))
    )
    (net (code "56") (name "VDD") (class "Default")
      (node (ref "C13") (pin "1") (pinfunction "1_1") (pintype "passive"))
      (node (ref "C14") (pin "1") (pinfunction "1_1") (pintype "passive"))
      (node (ref "C2") (pin "1") (pinfunction "1_1") (pintype "passive"))
      (node (ref "C3") (pin "1") (pinfunction "1_1") (pintype "passive"))
      (node (ref "R11") (pin "2") (pinfunction "2_2") (pintype "passive"))
      (node (ref "R13") (pin "2") (pinfunction "2_2") (pintype "passive"))
      (node (ref "R15") (pin "2") (pinfunction "2_2") (pintype "passive"))
      (node (ref "R16") (pin "2") (pinfunction "2_2") (pintype "passive"))
      (node (ref "R18") (pin "1") (pinfunction "1_1") (pintype "passive"))
      (node (ref "R20") (pin "1") (pinfunction "1_1") (pintype "passive"))
      (node (ref "R22") (pin "2") (pinfunction "2_2") (pintype "passive"))
      (node (ref "R23") (pin "2") (pinfunction "2_2") (pintype "passive"))
      (node (ref "R25") (pin "2") (pinfunction "2_2") (pintype "passive"))
      (node (ref "R27") (pin "2") (pinfunction "2_2") (pintype "passive"))
      (node (ref "R29") (pin "2") (pinfunction "2_2") (pintype "passive"))
      (node (ref "R3") (pin "2") (pinfunction "2_2") (pintype "passive"))
      (node (ref "R31") (pin "2") (pinfunction "2_2") (pintype "passive"))
      (node (ref "R33") (pin "2") (pinfunction "2_2") (pintype "passive"))
      (node (ref "R4") (pin "2") (pinfunction "2_2") (pintype "passive"))
      (node (ref "R5") (pin "2") (pinfunction "2_2") (pintype "passive"))
      (node (ref "R6") (pin "2") (pinfunction "2_2") (pintype "passive"))
      (node (ref "R7") (pin "2") (pinfunction "2_2") (pintype "passive"))
      (node (ref "R9") (pin "2") (pinfunction "2_2") (pintype "passive"))
      (node (ref "SV3") (pin "2") (pinfunction "2_2") (pintype "passive"))
      (node (ref "U$1") (pin "13") (pinfunction "P$13_13") (pintype "bidirectional"))
      (node (ref "U$1") (pin "14") (pinfunction "P$14_14") (pintype "bidirectional"))
      (node (ref "U$17") (pin "1") (pinfunction "G_1") (pintype "bidirectional"))
      (node (ref "U$18") (pin "1") (pinfunction "G_1") (pintype "bidirectional"))
      (node (ref "U$19") (pin "1") (pinfunction "G_1") (pintype "bidirectional"))
      (node (ref "U$20") (pin "1") (pinfunction "G_1") (pintype "bidirectional"))
      (node (ref "U$21") (pin "1") (pinfunction "G_1") (pintype "bidirectional"))
      (node (ref "U$22") (pin "1") (pinfunction "G_1") (pintype "bidirectional"))
      (node (ref "U$4") (pin "3") (pinfunction "W#_3") (pintype "bidirectional"))
      (node (ref "U$4") (pin "7") (pinfunction "H#_7") (pintype "bidirectional"))
      (node (ref "U$4") (pin "8") (pinfunction "VCC_8") (pintype "bidirectional"))
      (node (ref "U$5") (pin "OUT") (pinfunction "OUT_OUT") (pintype "output"))
      (node (ref "U$6") (pin "1") (pinfunction "G_1") (pintype "bidirectional"))
      (node (ref "U$7") (pin "1") (pinfunction "G_1") (pintype "bidirectional"))
      (node (ref "U$8") (pin "1") (pinfunction "G_1") (pintype "bidirectional"))
      (node (ref "U$9") (pin "1") (pinfunction "G_1") (pintype "bidirectional"))
    )
    (net (code "57") (name "unconnected-(U$1-P$2-Pad2)") (class "Default")
      (node (ref "U$1") (pin "2") (pinfunction "P$2_2") (pintype "bidirectional"))
    )
    (net (code "58") (name "unconnected-(U$1-P$3-Pad3)") (class "Default")
      (node (ref "U$1") (pin "3") (pinfunction "P$3_3") (pintype "bidirectional"))
    )
    (net (code "59") (name "unconnected-(U$1-P$6-Pad6)") (class "Default")
      (node (ref "U$1") (pin "6") (pinfunction "P$6_6") (pintype "bidirectional"))
    )
    (net (code "60") (name "unconnected-(U$1-P$7-Pad7)") (class "Default")
      (node (ref "U$1") (pin "7") (pinfunction "P$7_7") (pintype "bidirectional"))
    )
    (net (code "61") (name "unconnected-(U$1-P$8-Pad8)") (class "Default")
      (node (ref "U$1") (pin "8") (pinfunction "P$8_8") (pintype "bidirectional"))
    )
    (net (code "62") (name "unconnected-(U$1-P$9-Pad9)") (class "Default")
      (node (ref "U$1") (pin "9") (pinfunction "P$9_9") (pintype "bidirectional"))
    )
    (net (code "63") (name "unconnected-(U$1-P$10-Pad10)") (class "Default")
      (node (ref "U$1") (pin "10") (pinfunction "P$10_10") (pintype "bidirectional"))
    )
    (net (code "64") (name "unconnected-(U$1-P$15-Pad15)") (class "Default")
      (node (ref "U$1") (pin "15") (pinfunction "P$15_15") (pintype "bidirectional"))
    )
    (net (code "65") (name "unconnected-(U$1-P$16-Pad16)") (class "Default")
      (node (ref "U$1") (pin "16") (pinfunction "P$16_16") (pintype "bidirectional"))
    )
    (net (code "66") (name "unconnected-(U$1-P$18-Pad18)") (class "Default")
      (node (ref "U$1") (pin "18") (pinfunction "P$18_18") (pintype "bidirectional"))
    )
    (net (code "67") (name "unconnected-(U$1-P$26-Pad26)") (class "Default")
      (node (ref "U$1") (pin "26") (pinfunction "P$26_26") (pintype "bidirectional"))
    )
    (net (code "68") (name "unconnected-(U$1-P$27-Pad27)") (class "Default")
      (node (ref "U$1") (pin "27") (pinfunction "P$27_27") (pintype "bidirectional"))
    )
    (net (code "69") (name "unconnected-(U$1-P$32-Pad32)") (class "Default")
      (node (ref "U$1") (pin "32") (pinfunction "P$32_32") (pintype "bidirectional"))
    )
    (net (code "70") (name "unconnected-(U$1-P$33-Pad33)") (class "Default")
      (node (ref "U$1") (pin "33") (pinfunction "P$33_33") (pintype "bidirectional"))
    )
    (net (code "71") (name "unconnected-(U$1-P$34-Pad34)") (class "Default")
      (node (ref "U$1") (pin "34") (pinfunction "P$34_34") (pintype "bidirectional"))
    )
    (net (code "72") (name "unconnected-(U$1-P$35-Pad35)") (class "Default")
      (node (ref "U$1") (pin "35") (pinfunction "P$35_35") (pintype "bidirectional"))
    )
    (net (code "73") (name "unconnected-(U$1-P$36-Pad36)") (class "Default")
      (node (ref "U$1") (pin "36") (pinfunction "P$36_36") (pintype "bidirectional"))
    )
    (net (code "74") (name "unconnected-(U$1-P$37-Pad37)") (class "Default")
      (node (ref "U$1") (pin "37") (pinfunction "P$37_37") (pintype "bidirectional"))
    )
    (net (code "75") (name "unconnected-(U$1-P$38-Pad38)") (class "Default")
      (node (ref "U$1") (pin "38") (pinfunction "P$38_38") (pintype "bidirectional"))
    )
    (net (code "76") (name "unconnected-(U$1-P$39-Pad39)") (class "Default")
      (node (ref "U$1") (pin "39") (pinfunction "P$39_39") (pintype "bidirectional"))
    )
    (net (code "77") (name "unconnected-(U$1-P$40-Pad40)") (class "Default")
      (node (ref "U$1") (pin "40") (pinfunction "P$40_40") (pintype "bidirectional"))
    )
    (net (code "78") (name "unconnected-(U$1-P$41-Pad41)") (class "Default")
      (node (ref "U$1") (pin "41") (pinfunction "P$41_41") (pintype "bidirectional"))
    )
    (net (code "79") (name "unconnected-(U$1-P$42-Pad42)") (class "Default")
      (node (ref "U$1") (pin "42") (pinfunction "P$42_42") (pintype "bidirectional"))
    )
    (net (code "80") (name "unconnected-(U$1-P$43-Pad43)") (class "Default")
      (node (ref "U$1") (pin "43") (pinfunction "P$43_43") (pintype "bidirectional"))
    )
    (net (code "81") (name "unconnected-(U1-(A8)PC0-Pad53)") (class "Default")
      (node (ref "U1") (pin "53") (pinfunction "(A8)PC0_53") (pintype "bidirectional"))
    )
    (net (code "82") (name "unconnected-(U1-(A9)PC1-Pad54)") (class "Default")
      (node (ref "U1") (pin "54") (pinfunction "(A9)PC1_54") (pintype "bidirectional"))
    )
    (net (code "83") (name "unconnected-(U1-(A10)PC2-Pad55)") (class "Default")
      (node (ref "U1") (pin "55") (pinfunction "(A10)PC2_55") (pintype "bidirectional"))
    )
    (net (code "84") (name "unconnected-(U1-(A11)PC3-Pad56)") (class "Default")
      (node (ref "U1") (pin "56") (pinfunction "(A11)PC3_56") (pintype "bidirectional"))
    )
    (net (code "85") (name "unconnected-(U1-(A12)PC4-Pad57)") (class "Default")
      (node (ref "U1") (pin "57") (pinfunction "(A12)PC4_57") (pintype "bidirectional"))
    )
    (net (code "86") (name "unconnected-(U1-(A13)PC5-Pad58)") (class "Default")
      (node (ref "U1") (pin "58") (pinfunction "(A13)PC5_58") (pintype "bidirectional"))
    )
    (net (code "87") (name "unconnected-(U1-(A14)PC6-Pad59)") (class "Default")
      (node (ref "U1") (pin "59") (pinfunction "(A14)PC6_59") (pintype "bidirectional"))
    )
    (net (code "88") (name "unconnected-(U1-(A15)PC7-Pad60)") (class "Default")
      (node (ref "U1") (pin "60") (pinfunction "(A15)PC7_60") (pintype "bidirectional"))
    )
    (net (code "89") (name "unconnected-(U1-(AD1)PA1-Pad77)") (class "Default")
      (node (ref "U1") (pin "77") (pinfunction "(AD1)PA1_77") (pintype "bidirectional"))
    )
    (net (code "90") (name "unconnected-(U1-(AD2)PA2-Pad76)") (class "Default")
      (node (ref "U1") (pin "76") (pinfunction "(AD2)PA2_76") (pintype "bidirectional"))
    )
    (net (code "91") (name "unconnected-(U1-(AD3)PA3-Pad75)") (class "Default")
      (node (ref "U1") (pin "75") (pinfunction "(AD3)PA3_75") (pintype "bidirectional"))
    )
    (net (code "92") (name "unconnected-(U1-(AD4)PA4-Pad74)") (class "Default")
      (node (ref "U1") (pin "74") (pinfunction "(AD4)PA4_74") (pintype "bidirectional"))
    )
    (net (code "93") (name "unconnected-(U1-(AD5)PA5-Pad73)") (class "Default")
      (node (ref "U1") (pin "73") (pinfunction "(AD5)PA5_73") (pintype "bidirectional"))
    )
    (net (code "94") (name "unconnected-(U1-(AD6)PA6-Pad72)") (class "Default")
      (node (ref "U1") (pin "72") (pinfunction "(AD6)PA6_72") (pintype "bidirectional"))
    )
    (net (code "95") (name "unconnected-(U1-(AD7)PA7-Pad71)") (class "Default")
      (node (ref "U1") (pin "71") (pinfunction "(AD7)PA7_71") (pintype "bidirectional"))
    )
    (net (code "96") (name "unconnected-(U1-(ADC1)PF1-Pad96)") (class "Default")
      (node (ref "U1") (pin "96") (pinfunction "(ADC1)PF1_96") (pintype "bidirectional"))
    )
    (net (code "97") (name "unconnected-(U1-(ADC2)PF2-Pad95)") (class "Default")
      (node (ref "U1") (pin "95") (pinfunction "(ADC2)PF2_95") (pintype "bidirectional"))
    )
    (net (code "98") (name "unconnected-(U1-(ADC3)PF3-Pad94)") (class "Default")
      (node (ref "U1") (pin "94") (pinfunction "(ADC3)PF3_94") (pintype "bidirectional"))
    )
    (net (code "99") (name "unconnected-(U1-(ALE)PG2-Pad70)") (class "Default")
      (node (ref "U1") (pin "70") (pinfunction "(ALE)PG2_70") (pintype "bidirectional"))
    )
    (net (code "100") (name "unconnected-(U1-(CLKO{slash}ICP3{slash}INT7)PE7-Pad9)") (class "Default")
      (node (ref "U1") (pin "9") (pinfunction "(CLKO/ICP3/INT7)PE7_9") (pintype "bidirectional"))
    )
    (net (code "101") (name "unconnected-(U1-(ICP1)PD4-Pad47)") (class "Default")
      (node (ref "U1") (pin "47") (pinfunction "(ICP1)PD4_47") (pintype "bidirectional"))
    )
    (net (code "102") (name "unconnected-(U1-(OC2A{slash}PCINT4)PB4-Pad23)") (class "Default")
      (node (ref "U1") (pin "23") (pinfunction "(OC2A/PCINT4)PB4_23") (pintype "bidirectional"))
    )
    (net (code "103") (name "unconnected-(U1-(RD)PG1-Pad52)") (class "Default")
      (node (ref "U1") (pin "52") (pinfunction "(RD)PG1_52") (pintype "bidirectional"))
    )
    (net (code "104") (name "unconnected-(U1-(RXD0{slash}PCIN8)PE0-Pad2)") (class "Default")
      (node (ref "U1") (pin "2") (pinfunction "(RXD0/PCIN8)PE0_2") (pintype "bidirectional"))
    )
    (net (code "105") (name "unconnected-(U1-(SCL{slash}INT0)PD0-Pad43)") (class "Default")
      (node (ref "U1") (pin "43") (pinfunction "(SCL/INT0)PD0_43") (pintype "bidirectional"))
    )
    (net (code "106") (name "unconnected-(U1-(SDA{slash}INT1)PD1-Pad44)") (class "Default")
      (node (ref "U1") (pin "44") (pinfunction "(SDA/INT1)PD1_44") (pintype "bidirectional"))
    )
    (net (code "107") (name "unconnected-(U1-(T0)PD7-Pad50)") (class "Default")
      (node (ref "U1") (pin "50") (pinfunction "(T0)PD7_50") (pintype "bidirectional"))
    )
    (net (code "108") (name "unconnected-(U1-(T1)PD6-Pad49)") (class "Default")
      (node (ref "U1") (pin "49") (pinfunction "(T1)PD6_49") (pintype "bidirectional"))
    )
    (net (code "109") (name "unconnected-(U1-(T3{slash}INT6)PE6-Pad8)") (class "Default")
      (node (ref "U1") (pin "8") (pinfunction "(T3/INT6)PE6_8") (pintype "bidirectional"))
    )
    (net (code "110") (name "unconnected-(U1-(TOSC1)PG4-Pad29)") (class "Default")
      (node (ref "U1") (pin "29") (pinfunction "(TOSC1)PG4_29") (pintype "bidirectional"))
    )
    (net (code "111") (name "unconnected-(U1-(TOSC2)PG3-Pad28)") (class "Default")
      (node (ref "U1") (pin "28") (pinfunction "(TOSC2)PG3_28") (pintype "bidirectional"))
    )
    (net (code "112") (name "unconnected-(U1-(TXD0)PE1-Pad3)") (class "Default")
      (node (ref "U1") (pin "3") (pinfunction "(TXD0)PE1_3") (pintype "bidirectional"))
    )
    (net (code "113") (name "unconnected-(U1-(WR)PG0-Pad51)") (class "Default")
      (node (ref "U1") (pin "51") (pinfunction "(WR)PG0_51") (pintype "bidirectional"))
    )
    (net (code "114") (name "unconnected-(U1-(XCK0{slash}AIN0)PE2-Pad4)") (class "Default")
      (node (ref "U1") (pin "4") (pinfunction "(XCK0/AIN0)PE2_4") (pintype "bidirectional"))
    )
    (net (code "115") (name "unconnected-(U1-(XCK1)PD5-Pad48)") (class "Default")
      (node (ref "U1") (pin "48") (pinfunction "(XCK1)PD5_48") (pintype "bidirectional"))
    )
    (net (code "116") (name "unconnected-(U1-AREF-Pad98)") (class "Default")
      (node (ref "U1") (pin "98") (pinfunction "AREF_98") (pintype "bidirectional"))
    )
    (net (code "117") (name "unconnected-(U1-PH2(XCK2)-Pad14)") (class "Default")
      (node (ref "U1") (pin "14") (pinfunction "PH2(XCK2)_14") (pintype "bidirectional"))
    )
    (net (code "118") (name "unconnected-(U1-PH6(OC2B)-Pad18)") (class "Default")
      (node (ref "U1") (pin "18") (pinfunction "PH6(OC2B)_18") (pintype "bidirectional"))
    )
    (net (code "119") (name "unconnected-(U1-PH7(T4)-Pad27)") (class "Default")
      (node (ref "U1") (pin "27") (pinfunction "PH7(T4)_27") (pintype "bidirectional"))
    )
    (net (code "120") (name "unconnected-(U1-PJ2(XCK3{slash}PCINT11)-Pad65)") (class "Default")
      (node (ref "U1") (pin "65") (pinfunction "PJ2(XCK3/PCINT11)_65") (pintype "bidirectional"))
    )
    (net (code "121") (name "unconnected-(U1-PJ3(PCINT12)-Pad66)") (class "Default")
      (node (ref "U1") (pin "66") (pinfunction "PJ3(PCINT12)_66") (pintype "bidirectional"))
    )
    (net (code "122") (name "unconnected-(U1-PJ4(PCINT13)-Pad67)") (class "Default")
      (node (ref "U1") (pin "67") (pinfunction "PJ4(PCINT13)_67") (pintype "bidirectional"))
    )
    (net (code "123") (name "unconnected-(U1-PJ5(PCINT14)-Pad68)") (class "Default")
      (node (ref "U1") (pin "68") (pinfunction "PJ5(PCINT14)_68") (pintype "bidirectional"))
    )
    (net (code "124") (name "unconnected-(U1-PJ6(PCINT15)-Pad69)") (class "Default")
      (node (ref "U1") (pin "69") (pinfunction "PJ6(PCINT15)_69") (pintype "bidirectional"))
    )
    (net (code "125") (name "unconnected-(U1-PJ7-Pad79)") (class "Default")
      (node (ref "U1") (pin "79") (pinfunction "PJ7_79") (pintype "bidirectional"))
    )
    (net (code "126") (name "unconnected-(U1-PK0(ADC8{slash}PCINT16)-Pad89)") (class "Default")
      (node (ref "U1") (pin "89") (pinfunction "PK0(ADC8/PCINT16)_89") (pintype "bidirectional"))
    )
    (net (code "127") (name "unconnected-(U1-PK1(ADC9{slash}PCINT17)-Pad88)") (class "Default")
      (node (ref "U1") (pin "88") (pinfunction "PK1(ADC9/PCINT17)_88") (pintype "bidirectional"))
    )
    (net (code "128") (name "unconnected-(U1-PK2(ADC10{slash}PCINT18)-Pad87)") (class "Default")
      (node (ref "U1") (pin "87") (pinfunction "PK2(ADC10/PCINT18)_87") (pintype "bidirectional"))
    )
    (net (code "129") (name "unconnected-(U1-PK3(ADC11{slash}PCINT19)-Pad86)") (class "Default")
      (node (ref "U1") (pin "86") (pinfunction "PK3(ADC11/PCINT19)_86") (pintype "bidirectional"))
    )
    (net (code "130") (name "unconnected-(U1-PK4(ADC12{slash}PCINT20)-Pad85)") (class "Default")
      (node (ref "U1") (pin "85") (pinfunction "PK4(ADC12/PCINT20)_85") (pintype "bidirectional"))
    )
    (net (code "131") (name "unconnected-(U1-PK5(ADC13{slash}PCINT21)-Pad84)") (class "Default")
      (node (ref "U1") (pin "84") (pinfunction "PK5(ADC13/PCINT21)_84") (pintype "bidirectional"))
    )
    (net (code "132") (name "unconnected-(U1-PK6(ADC14{slash}PCINT22)-Pad83)") (class "Default")
      (node (ref "U1") (pin "83") (pinfunction "PK6(ADC14/PCINT22)_83") (pintype "bidirectional"))
    )
    (net (code "133") (name "unconnected-(U1-PK7(ADC15{slash}PCINT23)-Pad82)") (class "Default")
      (node (ref "U1") (pin "82") (pinfunction "PK7(ADC15/PCINT23)_82") (pintype "bidirectional"))
    )
    (net (code "134") (name "unconnected-(U1-PL0(ICP4)-Pad35)") (class "Default")
      (node (ref "U1") (pin "35") (pinfunction "PL0(ICP4)_35") (pintype "bidirectional"))
    )
    (net (code "135") (name "unconnected-(U1-PL1(ICP5)-Pad36)") (class "Default")
      (node (ref "U1") (pin "36") (pinfunction "PL1(ICP5)_36") (pintype "bidirectional"))
    )
    (net (code "136") (name "unconnected-(U1-PL2(T5)-Pad37)") (class "Default")
      (node (ref "U1") (pin "37") (pinfunction "PL2(T5)_37") (pintype "bidirectional"))
    )
    (net (code "137") (name "unconnected-(U1-PL4(OC5B)-Pad39)") (class "Default")
      (node (ref "U1") (pin "39") (pinfunction "PL4(OC5B)_39") (pintype "bidirectional"))
    )
    (net (code "138") (name "unconnected-(U1-PL5(OC5C)-Pad40)") (class "Default")
      (node (ref "U1") (pin "40") (pinfunction "PL5(OC5C)_40") (pintype "bidirectional"))
    )
    (net (code "139") (name "unconnected-(U1-PL6-Pad41)") (class "Default")
      (node (ref "U1") (pin "41") (pinfunction "PL6_41") (pintype "bidirectional"))
    )
    (net (code "140") (name "unconnected-(U1-PL7-Pad42)") (class "Default")
      (node (ref "U1") (pin "42") (pinfunction "PL7_42") (pintype "bidirectional"))
    )
  )
)
